# in4_single_v0_2.net
KiCad netlist of a schematic drawn in EAGLE
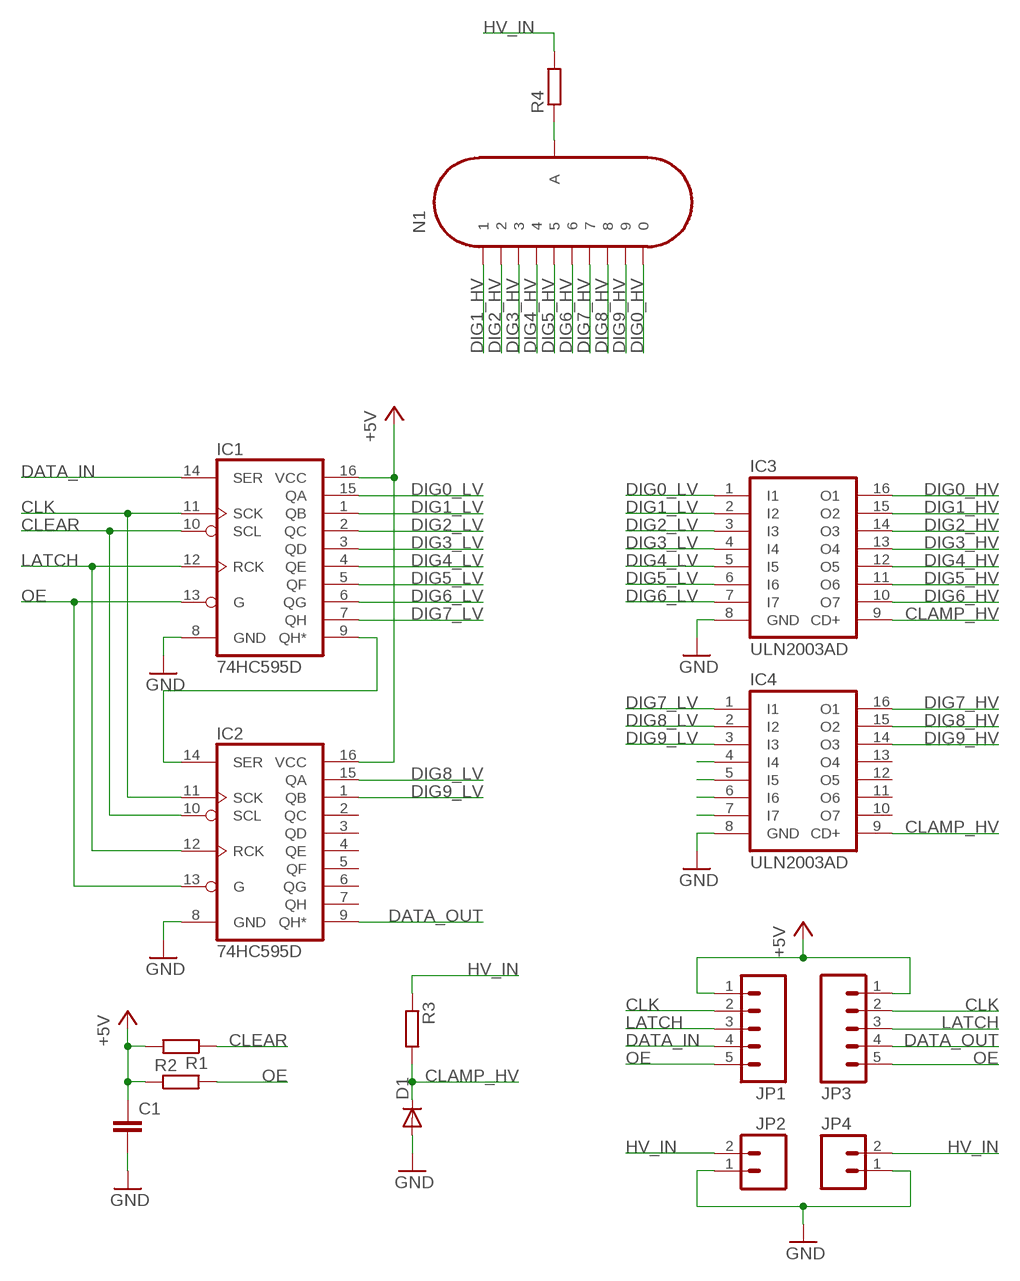
[diagram p0: schematic, sheet 1]

(export (version "E")
  (design (tool "Eeschema 10.0.6"))
  (components
    (comp (ref "C1")
      (value "C-EUC0805")
      (footprint "eagle-import:C0805")
      (libsource (lib "eagle-import") (part "C-EUC0805"))
    )
    (comp (ref "D1")
      (value "DIODE-SOD-123")
      (footprint "eagle-import:SOD-123")
      (libsource (lib "eagle-import") (part "DIODE-SOD-123"))
    )
    (comp (ref "IC1")
      (value "74HC595D")
      (footprint "eagle-import:SO16")
      (libsource (lib "eagle-import") (part "74595DLS"))
    )
    (comp (ref "IC2")
      (value "74HC595D")
      (footprint "eagle-import:SO16")
      (fields (field (name "PROD_ID") "IC-07875"))
      (libsource (lib "eagle-import") (part "74595DLS"))
    )
    (comp (ref "IC3")
      (value "ULN2003AD")
      (footprint "eagle-import:SO16")
      (libsource (lib "eagle-import") (part "ULN2003AD"))
    )
    (comp (ref "IC4")
      (value "ULN2003AD")
      (footprint "eagle-import:SO16")
      (libsource (lib "eagle-import") (part "ULN2003AD"))
    )
    (comp (ref "JP1")
      (value "M05NO_SILK")
      (footprint "eagle-import:1X05_NO_SILK")
      (libsource (lib "eagle-import") (part "M05NO_SILK"))
    )
    (comp (ref "JP2")
      (value "M021X02_NO_SILK")
      (footprint "eagle-import:1X02_NO_SILK")
      (libsource (lib "eagle-import") (part "M021X02_NO_SILK"))
    )
    (comp (ref "JP3")
      (value "M05NO_SILK")
      (footprint "eagle-import:1X05_NO_SILK")
      (libsource (lib "eagle-import") (part "M05NO_SILK"))
    )
    (comp (ref "JP4")
      (value "M021X02_NO_SILK")
      (footprint "eagle-import:1X02_NO_SILK")
      (libsource (lib "eagle-import") (part "M021X02_NO_SILK"))
    )
    (comp (ref "N1")
      (value "IN-4")
      (footprint "eagle-import:IN-4")
      (libsource (lib "eagle-import") (part "IN-4"))
    )
    (comp (ref "R1")
      (value "R-EU_R0805")
      (footprint "eagle-import:R0805")
      (libsource (lib "eagle-import") (part "R-EU_R0805"))
    )
    (comp (ref "R2")
      (value "R-EU_R0805")
      (footprint "eagle-import:R0805")
      (libsource (lib "eagle-import") (part "R-EU_R0805"))
    )
    (comp (ref "R3")
      (value "R-EU_R0805")
      (footprint "eagle-import:R0805")
      (libsource (lib "eagle-import") (part "R-EU_R0805"))
    )
    (comp (ref "R4")
      (value "R-EU_0204/7")
      (footprint "eagle-import:0204_7")
      (libsource (lib "eagle-import") (part "resistor_R-EU_0204/7"))
    )
  )
  (nets
    (net (code "1") (name "+5V") (class "Default")
      (node (ref "C1") (pin "1") (pinfunction "1_1") (pintype "passive"))
      (node (ref "IC1") (pin "16") (pinfunction "VCC_16") (pintype "power_in"))
      (node (ref "IC2") (pin "16") (pinfunction "VCC_16") (pintype "power_in"))
      (node (ref "JP1") (pin "1") (pinfunction "1_1") (pintype "passive"))
      (node (ref "JP3") (pin "1") (pinfunction "1_1") (pintype "passive"))
      (node (ref "R1") (pin "2") (pinfunction "2_2") (pintype "passive"))
      (node (ref "R2") (pin "1") (pinfunction "1_1") (pintype "passive"))
    )
    (net (code "2") (name "/CLAMP_HV") (class "Default")
      (node (ref "D1") (pin "C") (pinfunction "C_C") (pintype "passive"))
      (node (ref "IC3") (pin "9") (pinfunction "CD+_9") (pintype "passive"))
      (node (ref "IC4") (pin "9") (pinfunction "CD+_9") (pintype "passive"))
      (node (ref "R3") (pin "2") (pinfunction "2_2") (pintype "passive"))
    )
    (net (code "3") (name "/CLEAR") (class "Default")
      (node (ref "IC1") (pin "10") (pinfunction "SCL_10") (pintype "input"))
      (node (ref "IC2") (pin "10") (pinfunction "SCL_10") (pintype "input"))
      (node (ref "R1") (pin "1") (pinfunction "1_1") (pintype "passive"))
    )
    (net (code "4") (name "/CLK") (class "Default")
      (node (ref "IC1") (pin "11") (pinfunction "SCK_11") (pintype "input"))
      (node (ref "IC2") (pin "11") (pinfunction "SCK_11") (pintype "input"))
      (node (ref "JP1") (pin "2") (pinfunction "2_2") (pintype "passive"))
      (node (ref "JP3") (pin "2") (pinfunction "2_2") (pintype "passive"))
    )
    (net (code "5") (name "/DATA_IN") (class "Default")
      (node (ref "IC1") (pin "14") (pinfunction "SER_14") (pintype "input"))
      (node (ref "JP1") (pin "4") (pinfunction "4_4") (pintype "passive"))
    )
    (net (code "6") (name "/DATA_OUT") (class "Default")
      (node (ref "IC2") (pin "9") (pinfunction "QH*_9") (pintype "tri_state"))
      (node (ref "JP3") (pin "4") (pinfunction "4_4") (pintype "passive"))
    )
    (net (code "7") (name "/DIG0_HV") (class "Default")
      (node (ref "IC3") (pin "16") (pinfunction "O1_16") (pintype "open_collector"))
      (node (ref "N1") (pin "8") (pinfunction "0_8") (pintype "bidirectional"))
    )
    (net (code "8") (name "/DIG0_LV") (class "Default")
      (node (ref "IC1") (pin "15") (pinfunction "QA_15") (pintype "tri_state"))
      (node (ref "IC3") (pin "1") (pinfunction "I1_1") (pintype "input"))
    )
    (net (code "9") (name "/DIG1_HV") (class "Default")
      (node (ref "IC3") (pin "15") (pinfunction "O2_15") (pintype "open_collector"))
      (node (ref "N1") (pin "14") (pinfunction "1_14") (pintype "bidirectional"))
    )
    (net (code "10") (name "/DIG1_LV") (class "Default")
      (node (ref "IC1") (pin "1") (pinfunction "QB_1") (pintype "tri_state"))
      (node (ref "IC3") (pin "2") (pinfunction "I2_2") (pintype "input"))
    )
    (net (code "11") (name "/DIG2_HV") (class "Default")
      (node (ref "IC3") (pin "14") (pinfunction "O3_14") (pintype "open_collector"))
      (node (ref "N1") (pin "9") (pinfunction "2_9") (pintype "bidirectional"))
    )
    (net (code "12") (name "/DIG2_LV") (class "Default")
      (node (ref "IC1") (pin "2") (pinfunction "QC_2") (pintype "tri_state"))
      (node (ref "IC3") (pin "3") (pinfunction "I3_3") (pintype "input"))
    )
    (net (code "13") (name "/DIG3_HV") (class "Default")
      (node (ref "IC3") (pin "13") (pinfunction "O4_13") (pintype "open_collector"))
      (node (ref "N1") (pin "11") (pinfunction "3_11") (pintype "bidirectional"))
    )
    (net (code "14") (name "/DIG3_LV") (class "Default")
      (node (ref "IC1") (pin "3") (pinfunction "QD_3") (pintype "tri_state"))
      (node (ref "IC3") (pin "4") (pinfunction "I4_4") (pintype "input"))
    )
    (net (code "15") (name "/DIG4_HV") (class "Default")
      (node (ref "IC3") (pin "12") (pinfunction "O5_12") (pintype "open_collector"))
      (node (ref "N1") (pin "1") (pinfunction "4_1") (pintype "bidirectional"))
    )
    (net (code "16") (name "/DIG4_LV") (class "Default")
      (node (ref "IC1") (pin "4") (pinfunction "QE_4") (pintype "tri_state"))
      (node (ref "IC3") (pin "5") (pinfunction "I5_5") (pintype "input"))
    )
    (net (code "17") (name "/DIG5_HV") (class "Default")
      (node (ref "IC3") (pin "11") (pinfunction "O6_11") (pintype "open_collector"))
      (node (ref "N1") (pin "12") (pinfunction "5_12") (pintype "bidirectional"))
    )
    (net (code "18") (name "/DIG5_LV") (class "Default")
      (node (ref "IC1") (pin "5") (pinfunction "QF_5") (pintype "tri_state"))
      (node (ref "IC3") (pin "6") (pinfunction "I6_6") (pintype "input"))
    )
    (net (code "19") (name "/DIG6_HV") (class "Default")
      (node (ref "IC3") (pin "10") (pinfunction "O7_10") (pintype "open_collector"))
      (node (ref "N1") (pin "2") (pinfunction "6_2") (pintype "bidirectional"))
    )
    (net (code "20") (name "/DIG6_LV") (class "Default")
      (node (ref "IC1") (pin "6") (pinfunction "QG_6") (pintype "tri_state"))
      (node (ref "IC3") (pin "7") (pinfunction "I7_7") (pintype "input"))
    )
    (net (code "21") (name "/DIG7_HV") (class "Default")
      (node (ref "IC4") (pin "16") (pinfunction "O1_16") (pintype "open_collector"))
      (node (ref "N1") (pin "6") (pinfunction "7_6") (pintype "bidirectional"))
    )
    (net (code "22") (name "/DIG7_LV") (class "Default")
      (node (ref "IC1") (pin "7") (pinfunction "QH_7") (pintype "tri_state"))
      (node (ref "IC4") (pin "1") (pinfunction "I1_1") (pintype "input"))
    )
    (net (code "23") (name "/DIG8_HV") (class "Default")
      (node (ref "IC4") (pin "15") (pinfunction "O2_15") (pintype "open_collector"))
      (node (ref "N1") (pin "3") (pinfunction "8_3") (pintype "bidirectional"))
    )
    (net (code "24") (name "/DIG8_LV") (class "Default")
      (node (ref "IC2") (pin "15") (pinfunction "QA_15") (pintype "tri_state"))
      (node (ref "IC4") (pin "2") (pinfunction "I2_2") (pintype "input"))
    )
    (net (code "25") (name "/DIG9_HV") (class "Default")
      (node (ref "IC4") (pin "14") (pinfunction "O3_14") (pintype "open_collector"))
      (node (ref "N1") (pin "5") (pinfunction "9_5") (pintype "bidirectional"))
    )
    (net (code "26") (name "/DIG9_LV") (class "Default")
      (node (ref "IC2") (pin "1") (pinfunction "QB_1") (pintype "tri_state"))
      (node (ref "IC4") (pin "3") (pinfunction "I3_3") (pintype "input"))
    )
    (net (code "27") (name "/HV_IN") (class "Default")
      (node (ref "JP2") (pin "2") (pinfunction "2_2") (pintype "passive"))
      (node (ref "JP4") (pin "2") (pinfunction "2_2") (pintype "passive"))
      (node (ref "R3") (pin "1") (pinfunction "1_1") (pintype "passive"))
      (node (ref "R4") (pin "2") (pinfunction "2_2") (pintype "passive"))
    )
    (net (code "28") (name "/LATCH") (class "Default")
      (node (ref "IC1") (pin "12") (pinfunction "RCK_12") (pintype "input"))
      (node (ref "IC2") (pin "12") (pinfunction "RCK_12") (pintype "input"))
      (node (ref "JP1") (pin "3") (pinfunction "3_3") (pintype "passive"))
      (node (ref "JP3") (pin "3") (pinfunction "3_3") (pintype "passive"))
    )
    (net (code "29") (name "/OE") (class "Default")
      (node (ref "IC1") (pin "13") (pinfunction "G_13") (pintype "input"))
      (node (ref "IC2") (pin "13") (pinfunction "G_13") (pintype "input"))
      (node (ref "JP1") (pin "5") (pinfunction "5_5") (pintype "passive"))
      (node (ref "JP3") (pin "5") (pinfunction "5_5") (pintype "passive"))
      (node (ref "R2") (pin "2") (pinfunction "2_2") (pintype "passive"))
    )
    (net (code "30") (name "GND") (class "Default")
      (node (ref "C1") (pin "2") (pinfunction "2_2") (pintype "passive"))
      (node (ref "D1") (pin "A") (pinfunction "A_A") (pintype "passive"))
      (node (ref "IC1") (pin "8") (pinfunction "GND_8") (pintype "power_in"))
      (node (ref "IC2") (pin "8") (pinfunction "GND_8") (pintype "power_in"))
      (node (ref "IC3") (pin "8") (pinfunction "GND_8") (pintype "power_in"))
      (node (ref "IC4") (pin "8") (pinfunction "GND_8") (pintype "power_in"))
      (node (ref "JP2") (pin "1") (pinfunction "1_1") (pintype "passive"))
      (node (ref "JP4") (pin "1") (pinfunction "1_1") (pintype "passive"))
    )
    (net (code "31") (name "Net-(IC1-QH*)") (class "Default")
      (node (ref "IC1") (pin "9") (pinfunction "QH*_9") (pintype "tri_state"))
      (node (ref "IC2") (pin "14") (pinfunction "SER_14") (pintype "input"))
    )
    (net (code "32") (name "Net-(N1-A)") (class "Default")
      (node (ref "N1") (pin "4") (pinfunction "A_4") (pintype "bidirectional"))
      (node (ref "R4") (pin "1") (pinfunction "1_1") (pintype "passive"))
    )
    (net (code "33") (name "unconnected-(IC2-QC-Pad2)") (class "Default")
      (node (ref "IC2") (pin "2") (pinfunction "QC_2") (pintype "tri_state"))
    )
    (net (code "34") (name "unconnected-(IC2-QD-Pad3)") (class "Default")
      (node (ref "IC2") (pin "3") (pinfunction "QD_3") (pintype "tri_state"))
    )
    (net (code "35") (name "unconnected-(IC2-QE-Pad4)") (class "Default")
      (node (ref "IC2") (pin "4") (pinfunction "QE_4") (pintype "tri_state"))
    )
    (net (code "36") (name "unconnected-(IC2-QF-Pad5)") (class "Default")
      (node (ref "IC2") (pin "5") (pinfunction "QF_5") (pintype "tri_state"))
    )
    (net (code "37") (name "unconnected-(IC2-QG-Pad6)") (class "Default")
      (node (ref "IC2") (pin "6") (pinfunction "QG_6") (pintype "tri_state"))
    )
    (net (code "38") (name "unconnected-(IC2-QH-Pad7)") (class "Default")
      (node (ref "IC2") (pin "7") (pinfunction "QH_7") (pintype "tri_state"))
    )
    (net (code "39") (name "unconnected-(IC4-I4-Pad4)") (class "Default")
      (node (ref "IC4") (pin "4") (pinfunction "I4_4") (pintype "input"))
    )
    (net (code "40") (name "unconnected-(IC4-I5-Pad5)") (class "Default")
      (node (ref "IC4") (pin "5") (pinfunction "I5_5") (pintype "input"))
    )
    (net (code "41") (name "unconnected-(IC4-I6-Pad6)") (class "Default")
      (node (ref "IC4") (pin "6") (pinfunction "I6_6") (pintype "input"))
    )
    (net (code "42") (name "unconnected-(IC4-I7-Pad7)") (class "Default")
      (node (ref "IC4") (pin "7") (pinfunction "I7_7") (pintype "input"))
    )
    (net (code "43") (name "unconnected-(IC4-O4-Pad13)") (class "Default")
      (node (ref "IC4") (pin "13") (pinfunction "O4_13") (pintype "open_collector"))
    )
    (net (code "44") (name "unconnected-(IC4-O5-Pad12)") (class "Default")
      (node (ref "IC4") (pin "12") (pinfunction "O5_12") (pintype "open_collector"))
    )
    (net (code "45") (name "unconnected-(IC4-O6-Pad11)") (class "Default")
      (node (ref "IC4") (pin "11") (pinfunction "O6_11") (pintype "open_collector"))
    )
    (net (code "46") (name "unconnected-(IC4-O7-Pad10)") (class "Default")
      (node (ref "IC4") (pin "10") (pinfunction "O7_10") (pintype "open_collector"))
    )
  )
)
